# Impedance-Test-PCB.net
KiCad netlist of a schematic drawn in EAGLE
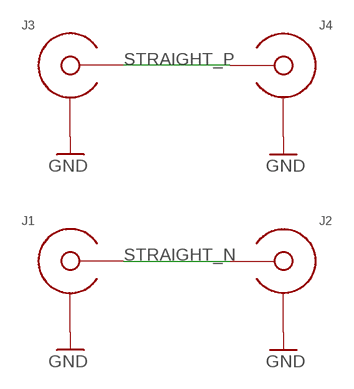
[diagram p0: schematic, sheet 1]

(export (version "E")
  (design (tool "Eeschema 10.0.6"))
  (components
    (comp (ref "J1")
      (value "SMA-EDGE-LAUNCH4020N4")
      (footprint "eagle-import:SMA-EDGE-LAUNCH-4L-4020-N4")
      (libsource (lib "eagle-import") (part "SMA-EDGE-LAUNCH4020N4"))
    )
    (comp (ref "J2")
      (value "SMA-EDGE-LAUNCH4020N4")
      (footprint "eagle-import:SMA-EDGE-LAUNCH-4L-4020-N4")
      (libsource (lib "eagle-import") (part "SMA-EDGE-LAUNCH4020N4"))
    )
    (comp (ref "J3")
      (value "SMA-EDGE-LAUNCH4020N4")
      (footprint "eagle-import:SMA-EDGE-LAUNCH-4L-4020-N4")
      (libsource (lib "eagle-import") (part "SMA-EDGE-LAUNCH4020N4"))
    )
    (comp (ref "J4")
      (value "SMA-EDGE-LAUNCH4020N4")
      (footprint "eagle-import:SMA-EDGE-LAUNCH-4L-4020-N4")
      (libsource (lib "eagle-import") (part "SMA-EDGE-LAUNCH4020N4"))
    )
  )
  (nets
    (net (code "1") (name "/STRAIGHT_N") (class "Default")
      (node (ref "J1") (pin "CENTER@1") (pinfunction "CENTER_CENTER@1") (pintype "bidirectional"))
      (node (ref "J1") (pin "CENTER@2") (pinfunction "CENTER_CENTER@2") (pintype "bidirectional"))
      (node (ref "J2") (pin "CENTER@1") (pinfunction "CENTER_CENTER@1") (pintype "bidirectional"))
      (node (ref "J2") (pin "CENTER@2") (pinfunction "CENTER_CENTER@2") (pintype "bidirectional"))
    )
    (net (code "2") (name "/STRAIGHT_P") (class "Default")
      (node (ref "J3") (pin "CENTER@1") (pinfunction "CENTER_CENTER@1") (pintype "bidirectional"))
      (node (ref "J3") (pin "CENTER@2") (pinfunction "CENTER_CENTER@2") (pintype "bidirectional"))
      (node (ref "J4") (pin "CENTER@1") (pinfunction "CENTER_CENTER@1") (pintype "bidirectional"))
      (node (ref "J4") (pin "CENTER@2") (pinfunction "CENTER_CENTER@2") (pintype "bidirectional"))
    )
    (net (code "3") (name "GND") (class "Default")
      (node (ref "J1") (pin "BOTTOM_GND") (pinfunction "SHIELD_BOTTOM_GND") (pintype "bidirectional"))
      (node (ref "J1") (pin "GND@1") (pinfunction "SHIELD_GND@1") (pintype "bidirectional"))
      (node (ref "J1") (pin "GND@10") (pinfunction "SHIELD_GND@10") (pintype "bidirectional"))
      (node (ref "J1") (pin "GND@14") (pinfunction "SHIELD_GND@14") (pintype "bidirectional"))
      (node (ref "J1") (pin "GND@15") (pinfunction "SHIELD_GND@15") (pintype "bidirectional"))
      (node (ref "J1") (pin "GND@16") (pinfunction "SHIELD_GND@16") (pintype "bidirectional"))
      (node (ref "J1") (pin "GND@17") (pinfunction "SHIELD_GND@17") (pintype "bidirectional"))
      (node (ref "J1") (pin "GND@2") (pinfunction "SHIELD_GND@2") (pintype "bidirectional"))
      (node (ref "J1") (pin "GND@3") (pinfunction "SHIELD_GND@3") (pintype "bidirectional"))
      (node (ref "J1") (pin "GND@4") (pinfunction "SHIELD_GND@4") (pintype "bidirectional"))
      (node (ref "J1") (pin "GND@5") (pinfunction "SHIELD_GND@5") (pintype "bidirectional"))
      (node (ref "J1") (pin "GND@6") (pinfunction "SHIELD_GND@6") (pintype "bidirectional"))
      (node (ref "J1") (pin "GND@7") (pinfunction "SHIELD_GND@7") (pintype "bidirectional"))
      (node (ref "J1") (pin "GND@8") (pinfunction "SHIELD_GND@8") (pintype "bidirectional"))
      (node (ref "J1") (pin "GND@9") (pinfunction "SHIELD_GND@9") (pintype "bidirectional"))
      (node (ref "J1") (pin "GND_PAD1") (pinfunction "SHIELD_GND_PAD1") (pintype "bidirectional"))
      (node (ref "J1") (pin "GND_PAD2") (pinfunction "SHIELD_GND_PAD2") (pintype "bidirectional"))
      (node (ref "J1") (pin "P$1") (pinfunction "SHIELD_P$1") (pintype "bidirectional"))
      (node (ref "J1") (pin "P$2") (pinfunction "SHIELD_P$2") (pintype "bidirectional"))
      (node (ref "J1") (pin "P$3") (pinfunction "SHIELD_P$3") (pintype "bidirectional"))
      (node (ref "J1") (pin "P$4") (pinfunction "SHIELD_P$4") (pintype "bidirectional"))
      (node (ref "J1") (pin "P$5") (pinfunction "SHIELD_P$5") (pintype "bidirectional"))
      (node (ref "J2") (pin "BOTTOM_GND") (pinfunction "SHIELD_BOTTOM_GND") (pintype "bidirectional"))
      (node (ref "J2") (pin "GND@1") (pinfunction "SHIELD_GND@1") (pintype "bidirectional"))
      (node (ref "J2") (pin "GND@10") (pinfunction "SHIELD_GND@10") (pintype "bidirectional"))
      (node (ref "J2") (pin "GND@14") (pinfunction "SHIELD_GND@14") (pintype "bidirectional"))
      (node (ref "J2") (pin "GND@15") (pinfunction "SHIELD_GND@15") (pintype "bidirectional"))
      (node (ref "J2") (pin "GND@16") (pinfunction "SHIELD_GND@16") (pintype "bidirectional"))
      (node (ref "J2") (pin "GND@17") (pinfunction "SHIELD_GND@17") (pintype "bidirectional"))
      (node (ref "J2") (pin "GND@2") (pinfunction "SHIELD_GND@2") (pintype "bidirectional"))
      (node (ref "J2") (pin "GND@3") (pinfunction "SHIELD_GND@3") (pintype "bidirectional"))
      (node (ref "J2") (pin "GND@4") (pinfunction "SHIELD_GND@4") (pintype "bidirectional"))
      (node (ref "J2") (pin "GND@5") (pinfunction "SHIELD_GND@5") (pintype "bidirectional"))
      (node (ref "J2") (pin "GND@6") (pinfunction "SHIELD_GND@6") (pintype "bidirectional"))
      (node (ref "J2") (pin "GND@7") (pinfunction "SHIELD_GND@7") (pintype "bidirectional"))
      (node (ref "J2") (pin "GND@8") (pinfunction "SHIELD_GND@8") (pintype "bidirectional"))
      (node (ref "J2") (pin "GND@9") (pinfunction "SHIELD_GND@9") (pintype "bidirectional"))
      (node (ref "J2") (pin "GND_PAD1") (pinfunction "SHIELD_GND_PAD1") (pintype "bidirectional"))
      (node (ref "J2") (pin "GND_PAD2") (pinfunction "SHIELD_GND_PAD2") (pintype "bidirectional"))
      (node (ref "J2") (pin "P$1") (pinfunction "SHIELD_P$1") (pintype "bidirectional"))
      (node (ref "J2") (pin "P$2") (pinfunction "SHIELD_P$2") (pintype "bidirectional"))
      (node (ref "J2") (pin "P$3") (pinfunction "SHIELD_P$3") (pintype "bidirectional"))
      (node (ref "J2") (pin "P$4") (pinfunction "SHIELD_P$4") (pintype "bidirectional"))
      (node (ref "J2") (pin "P$5") (pinfunction "SHIELD_P$5") (pintype "bidirectional"))
      (node (ref "J3") (pin "BOTTOM_GND") (pinfunction "SHIELD_BOTTOM_GND") (pintype "bidirectional"))
      (node (ref "J3") (pin "GND@1") (pinfunction "SHIELD_GND@1") (pintype "bidirectional"))
      (node (ref "J3") (pin "GND@10") (pinfunction "SHIELD_GND@10") (pintype "bidirectional"))
      (node (ref "J3") (pin "GND@14") (pinfunction "SHIELD_GND@14") (pintype "bidirectional"))
      (node (ref "J3") (pin "GND@15") (pinfunction "SHIELD_GND@15") (pintype "bidirectional"))
      (node (ref "J3") (pin "GND@16") (pinfunction "SHIELD_GND@16") (pintype "bidirectional"))
      (node (ref "J3") (pin "GND@17") (pinfunction "SHIELD_GND@17") (pintype "bidirectional"))
      (node (ref "J3") (pin "GND@2") (pinfunction "SHIELD_GND@2") (pintype "bidirectional"))
      (node (ref "J3") (pin "GND@3") (pinfunction "SHIELD_GND@3") (pintype "bidirectional"))
      (node (ref "J3") (pin "GND@4") (pinfunction "SHIELD_GND@4") (pintype "bidirectional"))
      (node (ref "J3") (pin "GND@5") (pinfunction "SHIELD_GND@5") (pintype "bidirectional"))
      (node (ref "J3") (pin "GND@6") (pinfunction "SHIELD_GND@6") (pintype "bidirectional"))
      (node (ref "J3") (pin "GND@7") (pinfunction "SHIELD_GND@7") (pintype "bidirectional"))
      (node (ref "J3") (pin "GND@8") (pinfunction "SHIELD_GND@8") (pintype "bidirectional"))
      (node (ref "J3") (pin "GND@9") (pinfunction "SHIELD_GND@9") (pintype "bidirectional"))
      (node (ref "J3") (pin "GND_PAD1") (pinfunction "SHIELD_GND_PAD1") (pintype "bidirectional"))
      (node (ref "J3") (pin "GND_PAD2") (pinfunction "SHIELD_GND_PAD2") (pintype "bidirectional"))
      (node (ref "J3") (pin "P$1") (pinfunction "SHIELD_P$1") (pintype "bidirectional"))
      (node (ref "J3") (pin "P$2") (pinfunction "SHIELD_P$2") (pintype "bidirectional"))
      (node (ref "J3") (pin "P$3") (pinfunction "SHIELD_P$3") (pintype "bidirectional"))
      (node (ref "J3") (pin "P$4") (pinfunction "SHIELD_P$4") (pintype "bidirectional"))
      (node (ref "J3") (pin "P$5") (pinfunction "SHIELD_P$5") (pintype "bidirectional"))
      (node (ref "J4") (pin "BOTTOM_GND") (pinfunction "SHIELD_BOTTOM_GND") (pintype "bidirectional"))
      (node (ref "J4") (pin "GND@1") (pinfunction "SHIELD_GND@1") (pintype "bidirectional"))
      (node (ref "J4") (pin "GND@10") (pinfunction "SHIELD_GND@10") (pintype "bidirectional"))
      (node (ref "J4") (pin "GND@14") (pinfunction "SHIELD_GND@14") (pintype "bidirectional"))
      (node (ref "J4") (pin "GND@15") (pinfunction "SHIELD_GND@15") (pintype "bidirectional"))
      (node (ref "J4") (pin "GND@16") (pinfunction "SHIELD_GND@16") (pintype "bidirectional"))
      (node (ref "J4") (pin "GND@17") (pinfunction "SHIELD_GND@17") (pintype "bidirectional"))
      (node (ref "J4") (pin "GND@2") (pinfunction "SHIELD_GND@2") (pintype "bidirectional"))
      (node (ref "J4") (pin "GND@3") (pinfunction "SHIELD_GND@3") (pintype "bidirectional"))
      (node (ref "J4") (pin "GND@4") (pinfunction "SHIELD_GND@4") (pintype "bidirectional"))
      (node (ref "J4") (pin "GND@5") (pinfunction "SHIELD_GND@5") (pintype "bidirectional"))
      (node (ref "J4") (pin "GND@6") (pinfunction "SHIELD_GND@6") (pintype "bidirectional"))
      (node (ref "J4") (pin "GND@7") (pinfunction "SHIELD_GND@7") (pintype "bidirectional"))
      (node (ref "J4") (pin "GND@8") (pinfunction "SHIELD_GND@8") (pintype "bidirectional"))
      (node (ref "J4") (pin "GND@9") (pinfunction "SHIELD_GND@9") (pintype "bidirectional"))
      (node (ref "J4") (pin "GND_PAD1") (pinfunction "SHIELD_GND_PAD1") (pintype "bidirectional"))
      (node (ref "J4") (pin "GND_PAD2") (pinfunction "SHIELD_GND_PAD2") (pintype "bidirectional"))
      (node (ref "J4") (pin "P$1") (pinfunction "SHIELD_P$1") (pintype "bidirectional"))
      (node (ref "J4") (pin "P$2") (pinfunction "SHIELD_P$2") (pintype "bidirectional"))
      (node (ref "J4") (pin "P$3") (pinfunction "SHIELD_P$3") (pintype "bidirectional"))
      (node (ref "J4") (pin "P$4") (pinfunction "SHIELD_P$4") (pintype "bidirectional"))
      (node (ref "J4") (pin "P$5") (pinfunction "SHIELD_P$5") (pintype "bidirectional"))
    )
  )
)
